# Servo.net
KiCad netlist of a schematic drawn in Altium Designer
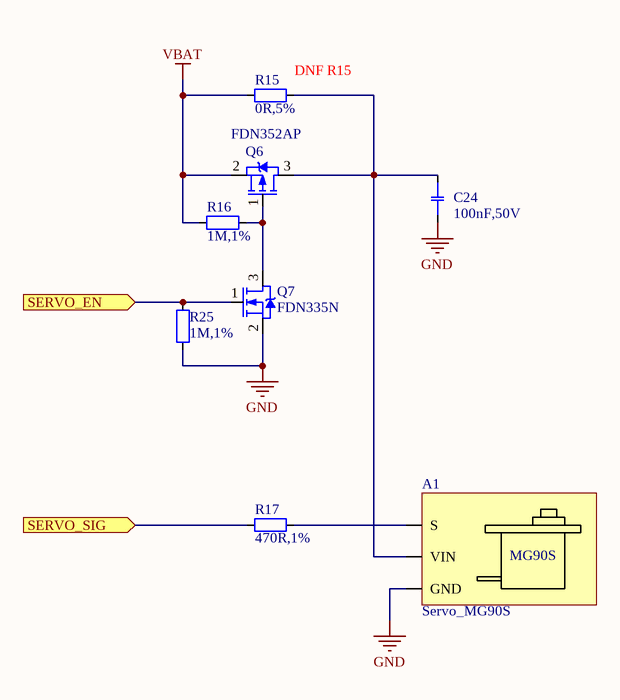
[diagram p0: Servo.SchDoc]

(export (version "E")
  (design (tool "Eeschema 10.0.6"))
  (components
    (comp (ref "A1")
      (value "Servo_MG90S")
      (footprint "SERVO_MG90S")
      (libsource (lib "Common") (part "Servo_MG90S"))
    )
    (comp (ref "C24")
      (value "100nF,50V")
      (footprint "CAPC1608X09N_0603")
      (description "CAP CER 0.1UF 50V 10% X7R 0603")
      (fields (field (name "MANUFACTURER") "Kemet") (field (name "TOLERANCE") "10%"))
      (libsource (lib "library") (part "CAP-NP_1"))
    )
    (comp (ref "Q6")
      (value "FDN352AP")
      (footprint "SOT95P230X110-3N_SOT23")
      (description "MOSFET P-CH 30V 1.3A SSOT-3")
      (fields (field (name "MANUFACTURER") "Fairchild"))
      (libsource (lib "library") (part "MOSFET-P_1"))
    )
    (comp (ref "Q7")
      (value "FDN335N")
      (footprint "SOT95P230X110-3N_SOT23")
      (description "MOSFET N-CH 20V 1.7A SSOT3")
      (fields (field (name "MANUFACTURER") "Fairchild Semiconductor"))
      (libsource (lib "library") (part "MOSFET-N_1"))
    )
    (comp (ref "R15")
      (value "0R,5%")
      (footprint "RESC1608X06N_0603")
      (description "RES 0.0 OHM 1/10W 0603 SMD")
      (fields (field (name "MANUFACTURER") "Yageo") (field (name "POWER") "0.1W"))
      (libsource (lib "") (part "RESISTOR_1_2"))
    )
    (comp (ref "R16")
      (value "1M,1%")
      (footprint "RESC1608X06N_0603")
      (description "RES 1.00M OHM 1/10W 1% 0603 SMD")
      (fields (field (name "MANUFACTURER") "Yageo") (field (name "POWER") "0.1W"))
      (libsource (lib "library") (part "RESISTOR_1"))
    )
    (comp (ref "R17")
      (value "470R,1%")
      (footprint "RESC1608X06N_0603")
      (description "RES 470 OHM 1/10W 1% 0603 SMD")
      (fields (field (name "MANUFACTURER") "Rohm Semiconductor") (field (name "POWER") "0.1W"))
      (libsource (lib "library") (part "RESISTOR_1"))
    )
    (comp (ref "R25")
      (value "1M,1%")
      (footprint "RESC1608X06N_0603")
      (description "RES 1.00M OHM 1/10W 1% 0603 SMD")
      (fields (field (name "MANUFACTURER") "Yageo") (field (name "POWER") "0.1W"))
      (libsource (lib "") (part "RESISTOR_1_1"))
    )
  )
  (nets
    (net (code "1") (name "/SERVO_EN") (class "Default")
      (node (ref "Q7") (pin "1") (pinfunction "G_1") (pintype "passive"))
      (node (ref "R25") (pin "1") (pinfunction "1_1") (pintype "passive"))
    )
    (net (code "2") (name "/SERVO_SIG") (class "Default")
      (node (ref "R17") (pin "2") (pinfunction "2_2") (pintype "passive"))
    )
    (net (code "3") (name "GND") (class "Default")
      (node (ref "A1") (pin "1") (pinfunction "GND_1") (pintype "passive"))
      (node (ref "C24") (pin "1") (pinfunction "1_1") (pintype "passive"))
      (node (ref "Q7") (pin "2") (pinfunction "S_2") (pintype "passive"))
      (node (ref "R25") (pin "2") (pinfunction "2_2") (pintype "passive"))
    )
    (net (code "4") (name "Net-(A1-S)") (class "Default")
      (node (ref "A1") (pin "3") (pinfunction "S_3") (pintype "passive"))
      (node (ref "R17") (pin "1") (pinfunction "1_1") (pintype "passive"))
    )
    (net (code "5") (name "Net-(A1-VIN)") (class "Default")
      (node (ref "A1") (pin "2") (pinfunction "VIN_2") (pintype "passive"))
      (node (ref "C24") (pin "2") (pinfunction "2_2") (pintype "passive"))
      (node (ref "Q6") (pin "3") (pinfunction "D_3") (pintype "passive"))
      (node (ref "R15") (pin "2") (pinfunction "2_2") (pintype "passive"))
    )
    (net (code "6") (name "Net-(Q6-G)") (class "Default")
      (node (ref "Q6") (pin "1") (pinfunction "G_1") (pintype "passive"))
      (node (ref "Q7") (pin "3") (pinfunction "D_3") (pintype "passive"))
      (node (ref "R16") (pin "1") (pinfunction "1_1") (pintype "passive"))
    )
    (net (code "7") (name "VBAT") (class "Default")
      (node (ref "Q6") (pin "2") (pinfunction "S_2") (pintype "passive"))
      (node (ref "R15") (pin "1") (pinfunction "1_1") (pintype "passive"))
      (node (ref "R16") (pin "2") (pinfunction "2_2") (pintype "passive"))
    )
  )
)
